# 10_FPGA_misc.net
KiCad netlist of a schematic drawn in Altium Designer
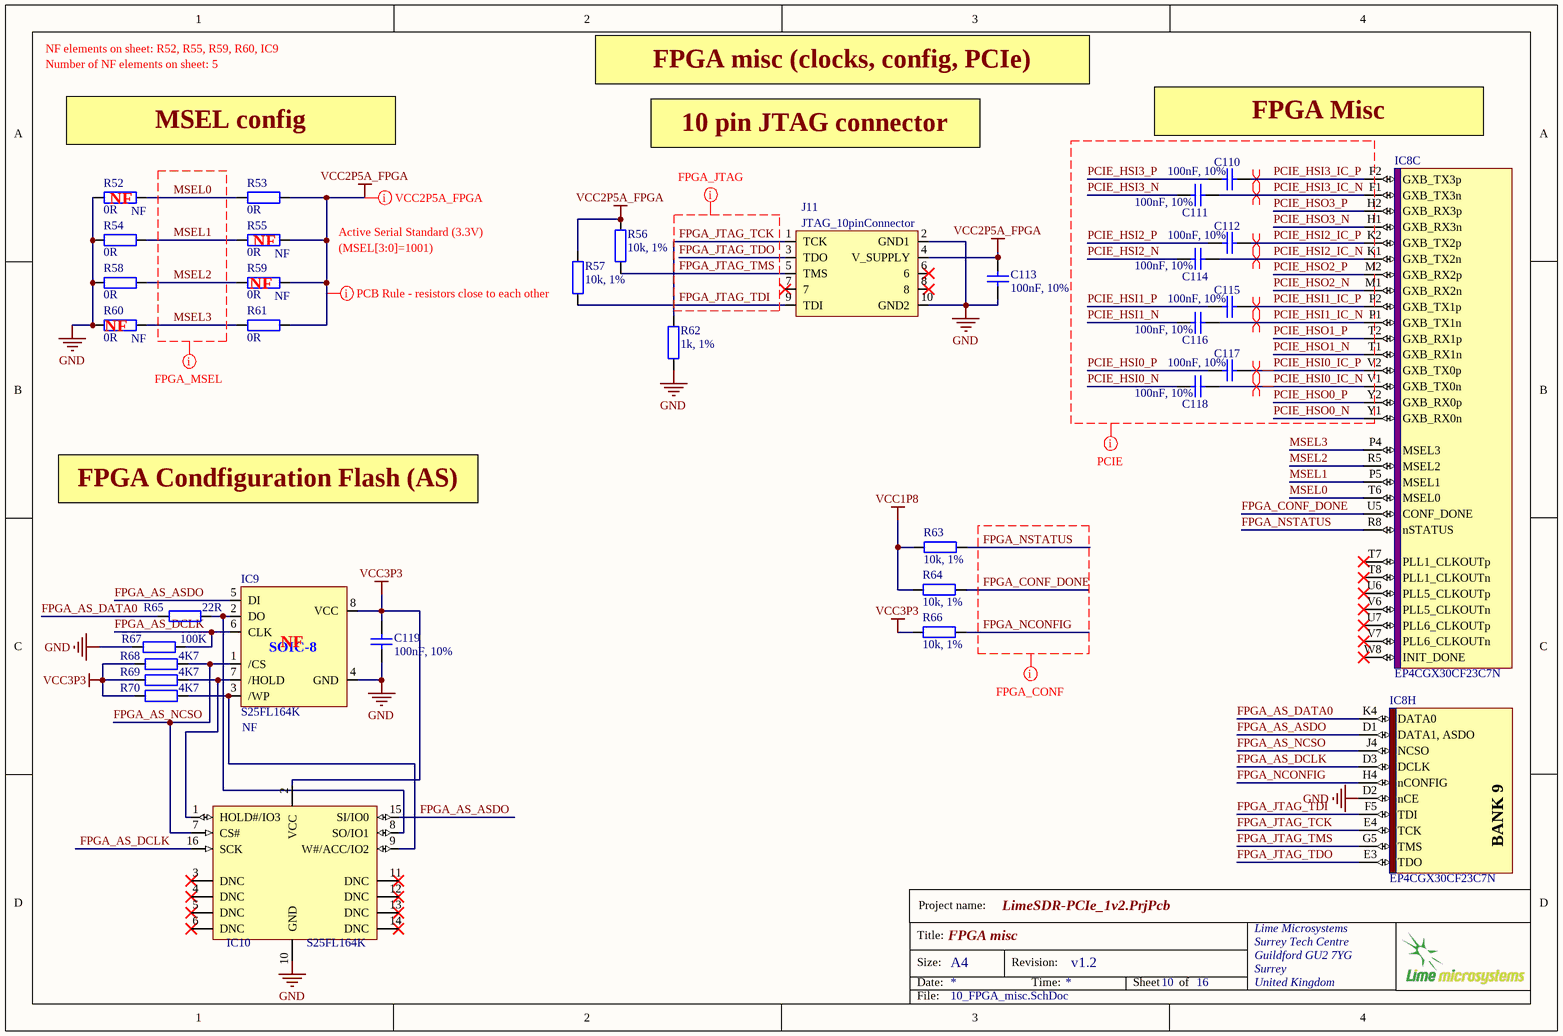
[diagram p0: 10_FPGA_misc.SchDoc]

(export (version "E")
  (design (tool "Eeschema 10.0.6"))
  (components
    (comp (ref "C110")
      (value "100nF, 10%")
      (footprint "CAP0402")
      (fields
        (field (name "TOLERANCE") "10 %")
        (field (name "MANUFACTURER") "Murata Electronics")
        (field (name "MANUFACTURER PART NUMBER") "GRM155R71C104KA88D")
      )
      (libsource (lib "LimeFPGAboard_schLib") (part "Cap_0603"))
    )
    (comp (ref "C111")
      (value "100nF, 10%")
      (footprint "CAP0402")
      (fields
        (field (name "TOLERANCE") "10 %")
        (field (name "MANUFACTURER") "Murata Electronics")
        (field (name "MANUFACTURER PART NUMBER") "GRM155R71C104KA88D")
      )
      (libsource (lib "LimeFPGAboard_schLib") (part "Cap_0603"))
    )
    (comp (ref "C112")
      (value "100nF, 10%")
      (footprint "CAP0402")
      (fields
        (field (name "TOLERANCE") "10 %")
        (field (name "MANUFACTURER") "Murata Electronics")
        (field (name "MANUFACTURER PART NUMBER") "GRM155R71C104KA88D")
      )
      (libsource (lib "LimeFPGAboard_schLib") (part "Cap_0603"))
    )
    (comp (ref "C113")
      (value "100nF, 10%")
      (footprint "CAP0402")
      (fields
        (field (name "TOLERANCE") "10 %")
        (field (name "MANUFACTURER") "Murata Electronics")
        (field (name "MANUFACTURER PART NUMBER") "GRM155R71C104KA88D")
      )
      (libsource (lib "LimeFPGAboard_schLib") (part "Cap_0603"))
    )
    (comp (ref "C114")
      (value "100nF, 10%")
      (footprint "CAP0402")
      (fields
        (field (name "TOLERANCE") "10 %")
        (field (name "MANUFACTURER") "Murata Electronics")
        (field (name "MANUFACTURER PART NUMBER") "GRM155R71C104KA88D")
      )
      (libsource (lib "LimeFPGAboard_schLib") (part "Cap_0603"))
    )
    (comp (ref "C115")
      (value "100nF, 10%")
      (footprint "CAP0402")
      (fields
        (field (name "TOLERANCE") "10 %")
        (field (name "MANUFACTURER") "Murata Electronics")
        (field (name "MANUFACTURER PART NUMBER") "GRM155R71C104KA88D")
      )
      (libsource (lib "LimeFPGAboard_schLib") (part "Cap_0603"))
    )
    (comp (ref "C116")
      (value "100nF, 10%")
      (footprint "CAP0402")
      (fields
        (field (name "TOLERANCE") "10 %")
        (field (name "MANUFACTURER") "Murata Electronics")
        (field (name "MANUFACTURER PART NUMBER") "GRM155R71C104KA88D")
      )
      (libsource (lib "LimeFPGAboard_schLib") (part "Cap_0603"))
    )
    (comp (ref "C117")
      (value "100nF, 10%")
      (footprint "CAP0402")
      (fields
        (field (name "TOLERANCE") "10 %")
        (field (name "MANUFACTURER") "Murata Electronics")
        (field (name "MANUFACTURER PART NUMBER") "GRM155R71C104KA88D")
      )
      (libsource (lib "LimeFPGAboard_schLib") (part "Cap_0603"))
    )
    (comp (ref "C118")
      (value "100nF, 10%")
      (footprint "CAP0402")
      (fields
        (field (name "TOLERANCE") "10 %")
        (field (name "MANUFACTURER") "Murata Electronics")
        (field (name "MANUFACTURER PART NUMBER") "GRM155R71C104KA88D")
      )
      (libsource (lib "LimeFPGAboard_schLib") (part "Cap_0603"))
    )
    (comp (ref "C119")
      (value "100nF, 10%")
      (footprint "CAP0402")
      (fields
        (field (name "TOLERANCE") "10 %")
        (field (name "MANUFACTURER") "Murata Electronics")
        (field (name "MANUFACTURER PART NUMBER") "GRM155R71C104KA88D")
      )
      (libsource (lib "LimeFPGAboard_schLib") (part "Cap_0603"))
    )
    (comp (ref "IC8")
      (value "EP4CGX30CF23C7N")
      (footprint "ALTR-FBGA484_A-200")
      (fields (field (name "MANUFACTURER") "Altera"))
      (libsource (lib "LimeMicroAltiumLib_schLib") (part "EP4CGX30CF23C7N"))
    )
    (comp (ref "IC9")
      (value "S25FL164K")
      (footprint "M25P40-VMN6TPB_SO8N")
      (fields (field (name "MANUFACTURER") "Cypress Semiconductor Corp") (field (name "ASSEMBLY INFO") "NF"))
      (libsource (lib "LimeMicroAltiumLib_schLib") (part "W25Q32FV"))
    )
    (comp (ref "IC10")
      (value "S25FL164K")
      (footprint "SOIC16_WIDE")
      (description "IC FLASH 64MBIT 108MHZ 16SOIC")
      (fields (field (name "MANUFACTURER") "Cypress Semiconductor Corp"))
      (libsource (lib "LimeMicroAltiumLib_schLib") (part "S25FL032P"))
    )
    (comp (ref "J11")
      (value "JTAG_10pinConnector")
      (footprint "HEADER5x2_SM")
      (fields (field (name "MANUFACTURER") "MOLEX"))
      (libsource (lib "LimeFPGAboard_schLib") (part "JTAG_connector_10pin"))
    )
    (comp (ref "R52")
      (value "0R")
      (footprint "RES0402")
      (fields (field (name "MANUFACTURER") "Yageo") (field (name "ASSEMBLY INFO") "NF"))
      (libsource (lib "LimeFPGAboard_schLib") (part "Res_0402"))
    )
    (comp (ref "R53")
      (value "0R")
      (footprint "RES0402")
      (fields (field (name "MANUFACTURER") "Yageo"))
      (libsource (lib "LimeFPGAboard_schLib") (part "Res_0402"))
    )
    (comp (ref "R54")
      (value "0R")
      (footprint "RES0402")
      (fields (field (name "MANUFACTURER") "Yageo"))
      (libsource (lib "LimeFPGAboard_schLib") (part "Res_0402"))
    )
    (comp (ref "R55")
      (value "0R")
      (footprint "RES0402")
      (fields (field (name "MANUFACTURER") "Yageo") (field (name "ASSEMBLY INFO") "NF"))
      (libsource (lib "LimeFPGAboard_schLib") (part "Res_0402"))
    )
    (comp (ref "R56")
      (value "10k, 1%")
      (footprint "RES0402")
      (fields (field (name "MANUFACTURER") "Yageo") (field (name "TOLERANCE") "±1%"))
      (libsource (lib "LimeMicroAltiumLib_schLib") (part "Res_0402"))
    )
    (comp (ref "R57")
      (value "10k, 1%")
      (footprint "RES0402")
      (fields (field (name "MANUFACTURER") "Yageo") (field (name "TOLERANCE") "±1%"))
      (libsource (lib "LimeMicroAltiumLib_schLib") (part "Res_0402"))
    )
    (comp (ref "R58")
      (value "0R")
      (footprint "RES0402")
      (fields (field (name "MANUFACTURER") "Yageo"))
      (libsource (lib "LimeFPGAboard_schLib") (part "Res_0402"))
    )
    (comp (ref "R59")
      (value "0R")
      (footprint "RES0402")
      (fields (field (name "MANUFACTURER") "Yageo") (field (name "ASSEMBLY INFO") "NF"))
      (libsource (lib "LimeFPGAboard_schLib") (part "Res_0402"))
    )
    (comp (ref "R60")
      (value "0R")
      (footprint "RES0402")
      (fields (field (name "MANUFACTURER") "Yageo") (field (name "ASSEMBLY INFO") "NF"))
      (libsource (lib "LimeFPGAboard_schLib") (part "Res_0402"))
    )
    (comp (ref "R61")
      (value "0R")
      (footprint "RES0402")
      (fields (field (name "MANUFACTURER") "Yageo"))
      (libsource (lib "LimeFPGAboard_schLib") (part "Res_0402"))
    )
    (comp (ref "R62")
      (value "1k, 1%")
      (footprint "RES0402")
      (fields (field (name "MANUFACTURER") "Stackpole Electronics Inc") (field (name "TOLERANCE") "±1%"))
      (libsource (lib "LimeMicroAltiumLib_schLib") (part "Res_0402"))
    )
    (comp (ref "R63")
      (value "10k, 1%")
      (footprint "RES0402")
      (fields (field (name "MANUFACTURER") "Yageo") (field (name "TOLERANCE") "±1%"))
      (libsource (lib "LimeMicroAltiumLib_schLib") (part "Res_0402"))
    )
    (comp (ref "R64")
      (value "10k, 1%")
      (footprint "RES0402")
      (fields (field (name "MANUFACTURER") "Yageo") (field (name "TOLERANCE") "±1%"))
      (libsource (lib "LimeMicroAltiumLib_schLib") (part "Res_0402"))
    )
    (comp (ref "R65")
      (value "22R")
      (footprint "RES0402")
      (fields (field (name "TOLERANCE") "±1%") (field (name "MANUFACTURER") "Yageo"))
      (libsource (lib "LimeFPGAboard_schLib") (part "Res_0402"))
    )
    (comp (ref "R66")
      (value "10k, 1%")
      (footprint "RES0402")
      (fields (field (name "MANUFACTURER") "Yageo") (field (name "TOLERANCE") "±1%"))
      (libsource (lib "LimeMicroAltiumLib_schLib") (part "Res_0402"))
    )
    (comp (ref "R67")
      (value "100K")
      (footprint "RES0402")
      (fields
        (field (name "TOLERANCE") "±5%")
        (field (name "MANUFACTURER") "Panasonic Electronic Components")
      )
      (libsource (lib "LimeFPGAboard_schLib") (part "Res_0402"))
    )
    (comp (ref "R68")
      (value "4K7")
      (footprint "RES0402")
      (fields (field (name "TOLERANCE") "±5%") (field (name "MANUFACTURER") "Stackpole Electronics Inc."))
      (libsource (lib "LimeFPGAboard_schLib") (part "Res_0402"))
    )
    (comp (ref "R69")
      (value "4K7")
      (footprint "RES0402")
      (fields (field (name "TOLERANCE") "±5%") (field (name "MANUFACTURER") "Stackpole Electronics Inc."))
      (libsource (lib "LimeFPGAboard_schLib") (part "Res_0402"))
    )
    (comp (ref "R70")
      (value "4K7")
      (footprint "RES0402")
      (fields (field (name "TOLERANCE") "±5%") (field (name "MANUFACTURER") "Stackpole Electronics Inc."))
      (libsource (lib "LimeFPGAboard_schLib") (part "Res_0402"))
    )
  )
  (nets
    (net (code "1") (name "/FPGA_AS_ASDO") (class "Default")
      (node (ref "IC10") (pin "15") (pinfunction "SI/IO0_15") (pintype "bidirectional"))
      (node (ref "IC8") (pin "D1") (pinfunction "DATA1,_ASDO_D1") (pintype "bidirectional"))
      (node (ref "IC9") (pin "5") (pinfunction "DI_5") (pintype "passive"))
    )
    (net (code "2") (name "/FPGA_AS_DATA0") (class "Default")
      (node (ref "IC8") (pin "K4") (pinfunction "DATA0_K4") (pintype "bidirectional"))
      (node (ref "R65") (pin "2") (pinfunction "2_2") (pintype "passive"))
    )
    (net (code "3") (name "/FPGA_AS_DCLK") (class "Default")
      (node (ref "IC10") (pin "16") (pinfunction "SCK_16") (pintype "input"))
      (node (ref "IC8") (pin "D3") (pinfunction "DCLK_D3") (pintype "bidirectional"))
      (node (ref "IC9") (pin "6") (pinfunction "CLK_6") (pintype "passive"))
      (node (ref "R67") (pin "1") (pinfunction "1_1") (pintype "passive"))
    )
    (net (code "4") (name "/FPGA_AS_NCSO") (class "Default")
      (node (ref "IC10") (pin "7") (pinfunction "CS#_7") (pintype "input"))
      (node (ref "IC8") (pin "J4") (pinfunction "NCSO_J4") (pintype "bidirectional"))
      (node (ref "IC9") (pin "1") (pinfunction "/CS_1") (pintype "passive"))
      (node (ref "R68") (pin "2") (pinfunction "2_2") (pintype "passive"))
    )
    (net (code "5") (name "/FPGA_CONF_DONE") (class "Default")
      (node (ref "IC8") (pin "U5") (pinfunction "CONF_DONE_U5") (pintype "bidirectional"))
      (node (ref "R64") (pin "2") (pinfunction "2_2") (pintype "passive"))
    )
    (net (code "6") (name "/FPGA_JTAG_TCK") (class "Default")
      (node (ref "IC8") (pin "E4") (pinfunction "TCK_E4") (pintype "bidirectional"))
      (node (ref "J11") (pin "1") (pinfunction "TCK_1") (pintype "passive"))
      (node (ref "R62") (pin "1") (pinfunction "1_1") (pintype "passive"))
    )
    (net (code "7") (name "/FPGA_JTAG_TDI") (class "Default")
      (node (ref "IC8") (pin "F5") (pinfunction "TDI_F5") (pintype "bidirectional"))
      (node (ref "J11") (pin "9") (pinfunction "TDI_9") (pintype "passive"))
      (node (ref "R57") (pin "2") (pinfunction "2_2") (pintype "passive"))
    )
    (net (code "8") (name "/FPGA_JTAG_TDO") (class "Default")
      (node (ref "IC8") (pin "E3") (pinfunction "TDO_E3") (pintype "bidirectional"))
      (node (ref "J11") (pin "3") (pinfunction "TDO_3") (pintype "passive"))
    )
    (net (code "9") (name "/FPGA_JTAG_TMS") (class "Default")
      (node (ref "IC8") (pin "G5") (pinfunction "TMS_G5") (pintype "bidirectional"))
      (node (ref "J11") (pin "5") (pinfunction "TMS_5") (pintype "passive"))
      (node (ref "R56") (pin "2") (pinfunction "2_2") (pintype "passive"))
    )
    (net (code "10") (name "/FPGA_NCONFIG") (class "Default")
      (node (ref "IC8") (pin "H4") (pinfunction "nCONFIG_H4") (pintype "bidirectional"))
      (node (ref "R66") (pin "2") (pinfunction "2_2") (pintype "passive"))
    )
    (net (code "11") (name "/FPGA_NSTATUS") (class "Default")
      (node (ref "IC8") (pin "R8") (pinfunction "nSTATUS_R8") (pintype "bidirectional"))
      (node (ref "R63") (pin "2") (pinfunction "2_2") (pintype "passive"))
    )
    (net (code "12") (name "/MSEL0") (class "Default")
      (node (ref "IC8") (pin "T6") (pinfunction "MSEL0_T6") (pintype "bidirectional"))
      (node (ref "R52") (pin "1") (pinfunction "1_1") (pintype "passive"))
      (node (ref "R53") (pin "2") (pinfunction "2_2") (pintype "passive"))
    )
    (net (code "13") (name "/MSEL1") (class "Default")
      (node (ref "IC8") (pin "P5") (pinfunction "MSEL1_P5") (pintype "bidirectional"))
      (node (ref "R54") (pin "1") (pinfunction "1_1") (pintype "passive"))
      (node (ref "R55") (pin "2") (pinfunction "2_2") (pintype "passive"))
    )
    (net (code "14") (name "/MSEL2") (class "Default")
      (node (ref "IC8") (pin "R5") (pinfunction "MSEL2_R5") (pintype "bidirectional"))
      (node (ref "R58") (pin "1") (pinfunction "1_1") (pintype "passive"))
      (node (ref "R59") (pin "2") (pinfunction "2_2") (pintype "passive"))
    )
    (net (code "15") (name "/MSEL3") (class "Default")
      (node (ref "IC8") (pin "P4") (pinfunction "MSEL3_P4") (pintype "bidirectional"))
      (node (ref "R60") (pin "1") (pinfunction "1_1") (pintype "passive"))
      (node (ref "R61") (pin "2") (pinfunction "2_2") (pintype "passive"))
    )
    (net (code "16") (name "/PCIE_HSI0_IC_N") (class "Default")
      (node (ref "C118") (pin "1") (pinfunction "1_1") (pintype "passive"))
      (node (ref "IC8") (pin "V1") (pinfunction "GXB_TX0n_V1") (pintype "bidirectional"))
    )
    (net (code "17") (name "/PCIE_HSI0_IC_P") (class "Default")
      (node (ref "C117") (pin "1") (pinfunction "1_1") (pintype "passive"))
      (node (ref "IC8") (pin "V2") (pinfunction "GXB_TX0p_V2") (pintype "bidirectional"))
    )
    (net (code "18") (name "/PCIE_HSI0_N") (class "Default")
      (node (ref "C118") (pin "2") (pinfunction "2_2") (pintype "passive"))
    )
    (net (code "19") (name "/PCIE_HSI0_P") (class "Default")
      (node (ref "C117") (pin "2") (pinfunction "2_2") (pintype "passive"))
    )
    (net (code "20") (name "/PCIE_HSI1_IC_N") (class "Default")
      (node (ref "C116") (pin "1") (pinfunction "1_1") (pintype "passive"))
      (node (ref "IC8") (pin "P1") (pinfunction "GXB_TX1n_P1") (pintype "bidirectional"))
    )
    (net (code "21") (name "/PCIE_HSI1_IC_P") (class "Default")
      (node (ref "C115") (pin "1") (pinfunction "1_1") (pintype "passive"))
      (node (ref "IC8") (pin "P2") (pinfunction "GXB_TX1p_P2") (pintype "bidirectional"))
    )
    (net (code "22") (name "/PCIE_HSI1_N") (class "Default")
      (node (ref "C116") (pin "2") (pinfunction "2_2") (pintype "passive"))
    )
    (net (code "23") (name "/PCIE_HSI1_P") (class "Default")
      (node (ref "C115") (pin "2") (pinfunction "2_2") (pintype "passive"))
    )
    (net (code "24") (name "/PCIE_HSI2_IC_N") (class "Default")
      (node (ref "C114") (pin "1") (pinfunction "1_1") (pintype "passive"))
      (node (ref "IC8") (pin "K1") (pinfunction "GXB_TX2n_K1") (pintype "bidirectional"))
    )
    (net (code "25") (name "/PCIE_HSI2_IC_P") (class "Default")
      (node (ref "C112") (pin "1") (pinfunction "1_1") (pintype "passive"))
      (node (ref "IC8") (pin "K2") (pinfunction "GXB_TX2p_K2") (pintype "bidirectional"))
    )
    (net (code "26") (name "/PCIE_HSI2_N") (class "Default")
      (node (ref "C114") (pin "2") (pinfunction "2_2") (pintype "passive"))
    )
    (net (code "27") (name "/PCIE_HSI2_P") (class "Default")
      (node (ref "C112") (pin "2") (pinfunction "2_2") (pintype "passive"))
    )
    (net (code "28") (name "/PCIE_HSI3_IC_N") (class "Default")
      (node (ref "C111") (pin "1") (pinfunction "1_1") (pintype "passive"))
      (node (ref "IC8") (pin "F1") (pinfunction "GXB_TX3n_F1") (pintype "bidirectional"))
    )
    (net (code "29") (name "/PCIE_HSI3_IC_P") (class "Default")
      (node (ref "C110") (pin "1") (pinfunction "1_1") (pintype "passive"))
      (node (ref "IC8") (pin "F2") (pinfunction "GXB_TX3p_F2") (pintype "bidirectional"))
    )
    (net (code "30") (name "/PCIE_HSI3_N") (class "Default")
      (node (ref "C111") (pin "2") (pinfunction "2_2") (pintype "passive"))
    )
    (net (code "31") (name "/PCIE_HSI3_P") (class "Default")
      (node (ref "C110") (pin "2") (pinfunction "2_2") (pintype "passive"))
    )
    (net (code "32") (name "/PCIE_HSO0_N") (class "Default")
      (node (ref "IC8") (pin "Y1") (pinfunction "GXB_RX0n_Y1") (pintype "bidirectional"))
    )
    (net (code "33") (name "/PCIE_HSO0_P") (class "Default")
      (node (ref "IC8") (pin "Y2") (pinfunction "GXB_RX0p_Y2") (pintype "bidirectional"))
    )
    (net (code "34") (name "/PCIE_HSO1_N") (class "Default")
      (node (ref "IC8") (pin "T1") (pinfunction "GXB_RX1n_T1") (pintype "bidirectional"))
    )
    (net (code "35") (name "/PCIE_HSO1_P") (class "Default")
      (node (ref "IC8") (pin "T2") (pinfunction "GXB_RX1p_T2") (pintype "bidirectional"))
    )
    (net (code "36") (name "/PCIE_HSO2_N") (class "Default")
      (node (ref "IC8") (pin "M1") (pinfunction "GXB_RX2n_M1") (pintype "bidirectional"))
    )
    (net (code "37") (name "/PCIE_HSO2_P") (class "Default")
      (node (ref "IC8") (pin "M2") (pinfunction "GXB_RX2p_M2") (pintype "bidirectional"))
    )
    (net (code "38") (name "/PCIE_HSO3_N") (class "Default")
      (node (ref "IC8") (pin "H1") (pinfunction "GXB_RX3n_H1") (pintype "bidirectional"))
    )
    (net (code "39") (name "/PCIE_HSO3_P") (class "Default")
      (node (ref "IC8") (pin "H2") (pinfunction "GXB_RX3p_H2") (pintype "bidirectional"))
    )
    (net (code "40") (name "GND") (class "Default")
      (node (ref "C113") (pin "2") (pinfunction "2_2") (pintype "passive"))
      (node (ref "C119") (pin "2") (pinfunction "2_2") (pintype "passive"))
      (node (ref "IC10") (pin "10") (pinfunction "GND_10") (pintype "passive"))
      (node (ref "IC8") (pin "D2") (pinfunction "nCE_D2") (pintype "bidirectional"))
      (node (ref "IC9") (pin "4") (pinfunction "GND_4") (pintype "passive"))
      (node (ref "J11") (pin "10") (pinfunction "GND2_10") (pintype "power_in"))
      (node (ref "J11") (pin "2") (pinfunction "GND1_2") (pintype "power_in"))
      (node (ref "R52") (pin "2") (pinfunction "2_2") (pintype "passive"))
      (node (ref "R54") (pin "2") (pinfunction "2_2") (pintype "passive"))
      (node (ref "R58") (pin "2") (pinfunction "2_2") (pintype "passive"))
      (node (ref "R60") (pin "2") (pinfunction "2_2") (pintype "passive"))
      (node (ref "R62") (pin "2") (pinfunction "2_2") (pintype "passive"))
      (node (ref "R67") (pin "2") (pinfunction "2_2") (pintype "passive"))
    )
    (net (code "41") (name "Net-(IC10-HOLD#{slash}IO3)") (class "Default")
      (node (ref "IC10") (pin "1") (pinfunction "HOLD#/IO3_1") (pintype "bidirectional"))
      (node (ref "IC9") (pin "7") (pinfunction "/HOLD_7") (pintype "passive"))
      (node (ref "R69") (pin "2") (pinfunction "2_2") (pintype "passive"))
    )
    (net (code "42") (name "Net-(IC10-SO{slash}IO1)") (class "Default")
      (node (ref "IC10") (pin "8") (pinfunction "SO/IO1_8") (pintype "bidirectional"))
      (node (ref "IC9") (pin "2") (pinfunction "DO_2") (pintype "passive"))
      (node (ref "R65") (pin "1") (pinfunction "1_1") (pintype "passive"))
    )
    (net (code "43") (name "Net-(IC10-W#{slash}ACC{slash}IO2)") (class "Default")
      (node (ref "IC10") (pin "9") (pinfunction "W#/ACC/IO2_9") (pintype "bidirectional"))
      (node (ref "IC9") (pin "3") (pinfunction "/WP_3") (pintype "passive"))
      (node (ref "R70") (pin "2") (pinfunction "2_2") (pintype "passive"))
    )
    (net (code "44") (name "VCC1P8") (class "Default")
      (node (ref "R63") (pin "1") (pinfunction "1_1") (pintype "passive"))
      (node (ref "R64") (pin "1") (pinfunction "1_1") (pintype "passive"))
    )
    (net (code "45") (name "VCC2P5A_FPGA") (class "Default")
      (node (ref "C113") (pin "1") (pinfunction "1_1") (pintype "passive"))
      (node (ref "J11") (pin "4") (pinfunction "V_SUPPLY_4") (pintype "power_in"))
      (node (ref "R53") (pin "1") (pinfunction "1_1") (pintype "passive"))
      (node (ref "R55") (pin "1") (pinfunction "1_1") (pintype "passive"))
      (node (ref "R56") (pin "1") (pinfunction "1_1") (pintype "passive"))
      (node (ref "R57") (pin "1") (pinfunction "1_1") (pintype "passive"))
      (node (ref "R59") (pin "1") (pinfunction "1_1") (pintype "passive"))
      (node (ref "R61") (pin "1") (pinfunction "1_1") (pintype "passive"))
    )
    (net (code "46") (name "VCC3P3") (class "Default")
      (node (ref "C119") (pin "1") (pinfunction "1_1") (pintype "passive"))
      (node (ref "IC10") (pin "2") (pinfunction "VCC_2") (pintype "power_in"))
      (node (ref "IC9") (pin "8") (pinfunction "VCC_8") (pintype "passive"))
      (node (ref "R66") (pin "1") (pinfunction "1_1") (pintype "passive"))
      (node (ref "R68") (pin "1") (pinfunction "1_1") (pintype "passive"))
      (node (ref "R69") (pin "1") (pinfunction "1_1") (pintype "passive"))
      (node (ref "R70") (pin "1") (pinfunction "1_1") (pintype "passive"))
    )
    (net (code "47") (name "unconnected-(IC8C-INIT_DONE-PadW8)") (class "Default")
      (node (ref "IC8") (pin "W8") (pinfunction "INIT_DONE_W8") (pintype "bidirectional+no_connect"))
    )
    (net (code "48") (name "unconnected-(IC8C-PLL1_CLKOUTn-PadT8)") (class "Default")
      (node (ref "IC8") (pin "T8") (pinfunction "PLL1_CLKOUTn_T8") (pintype "bidirectional+no_connect"))
    )
    (net (code "49") (name "unconnected-(IC8C-PLL1_CLKOUTp-PadT7)") (class "Default")
      (node (ref "IC8") (pin "T7") (pinfunction "PLL1_CLKOUTp_T7") (pintype "bidirectional+no_connect"))
    )
    (net (code "50") (name "unconnected-(IC8C-PLL5_CLKOUTn-PadV6)") (class "Default")
      (node (ref "IC8") (pin "V6") (pinfunction "PLL5_CLKOUTn_V6") (pintype "bidirectional+no_connect"))
    )
    (net (code "51") (name "unconnected-(IC8C-PLL5_CLKOUTp-PadU6)") (class "Default")
      (node (ref "IC8") (pin "U6") (pinfunction "PLL5_CLKOUTp_U6") (pintype "bidirectional+no_connect"))
    )
    (net (code "52") (name "unconnected-(IC8C-PLL6_CLKOUTn-PadV7)") (class "Default")
      (node (ref "IC8") (pin "V7") (pinfunction "PLL6_CLKOUTn_V7") (pintype "bidirectional+no_connect"))
    )
    (net (code "53") (name "unconnected-(IC8C-PLL6_CLKOUTp-PadU7)") (class "Default")
      (node (ref "IC8") (pin "U7") (pinfunction "PLL6_CLKOUTp_U7") (pintype "bidirectional+no_connect"))
    )
    (net (code "54") (name "unconnected-(IC10-DNC-Pad3)") (class "Default")
      (node (ref "IC10") (pin "3") (pinfunction "DNC_3") (pintype "passive+no_connect"))
    )
    (net (code "55") (name "unconnected-(IC10-DNC-Pad4)") (class "Default")
      (node (ref "IC10") (pin "4") (pinfunction "DNC_4") (pintype "passive+no_connect"))
    )
    (net (code "56") (name "unconnected-(IC10-DNC-Pad5)") (class "Default")
      (node (ref "IC10") (pin "5") (pinfunction "DNC_5") (pintype "passive+no_connect"))
    )
    (net (code "57") (name "unconnected-(IC10-DNC-Pad6)") (class "Default")
      (node (ref "IC10") (pin "6") (pinfunction "DNC_6") (pintype "passive+no_connect"))
    )
    (net (code "58") (name "unconnected-(IC10-DNC-Pad11)") (class "Default")
      (node (ref "IC10") (pin "11") (pinfunction "DNC_11") (pintype "passive+no_connect"))
    )
    (net (code "59") (name "unconnected-(IC10-DNC-Pad12)") (class "Default")
      (node (ref "IC10") (pin "12") (pinfunction "DNC_12") (pintype "passive+no_connect"))
    )
    (net (code "60") (name "unconnected-(IC10-DNC-Pad13)") (class "Default")
      (node (ref "IC10") (pin "13") (pinfunction "DNC_13") (pintype "passive+no_connect"))
    )
    (net (code "61") (name "unconnected-(IC10-DNC-Pad14)") (class "Default")
      (node (ref "IC10") (pin "14") (pinfunction "DNC_14") (pintype "passive+no_connect"))
    )
    (net (code "62") (name "unconnected-(J11-Pad6)") (class "Default")
      (node (ref "J11") (pin "6") (pinfunction "6_6") (pintype "passive+no_connect"))
    )
    (net (code "63") (name "unconnected-(J11-Pad7)") (class "Default")
      (node (ref "J11") (pin "7") (pinfunction "7_7") (pintype "passive+no_connect"))
    )
    (net (code "64") (name "unconnected-(J11-Pad8)") (class "Default")
      (node (ref "J11") (pin "8") (pinfunction "8_8") (pintype "passive+no_connect"))
    )
  )
)
